# EMG_digital_Part.net
KiCad netlist of a schematic drawn in EAGLE
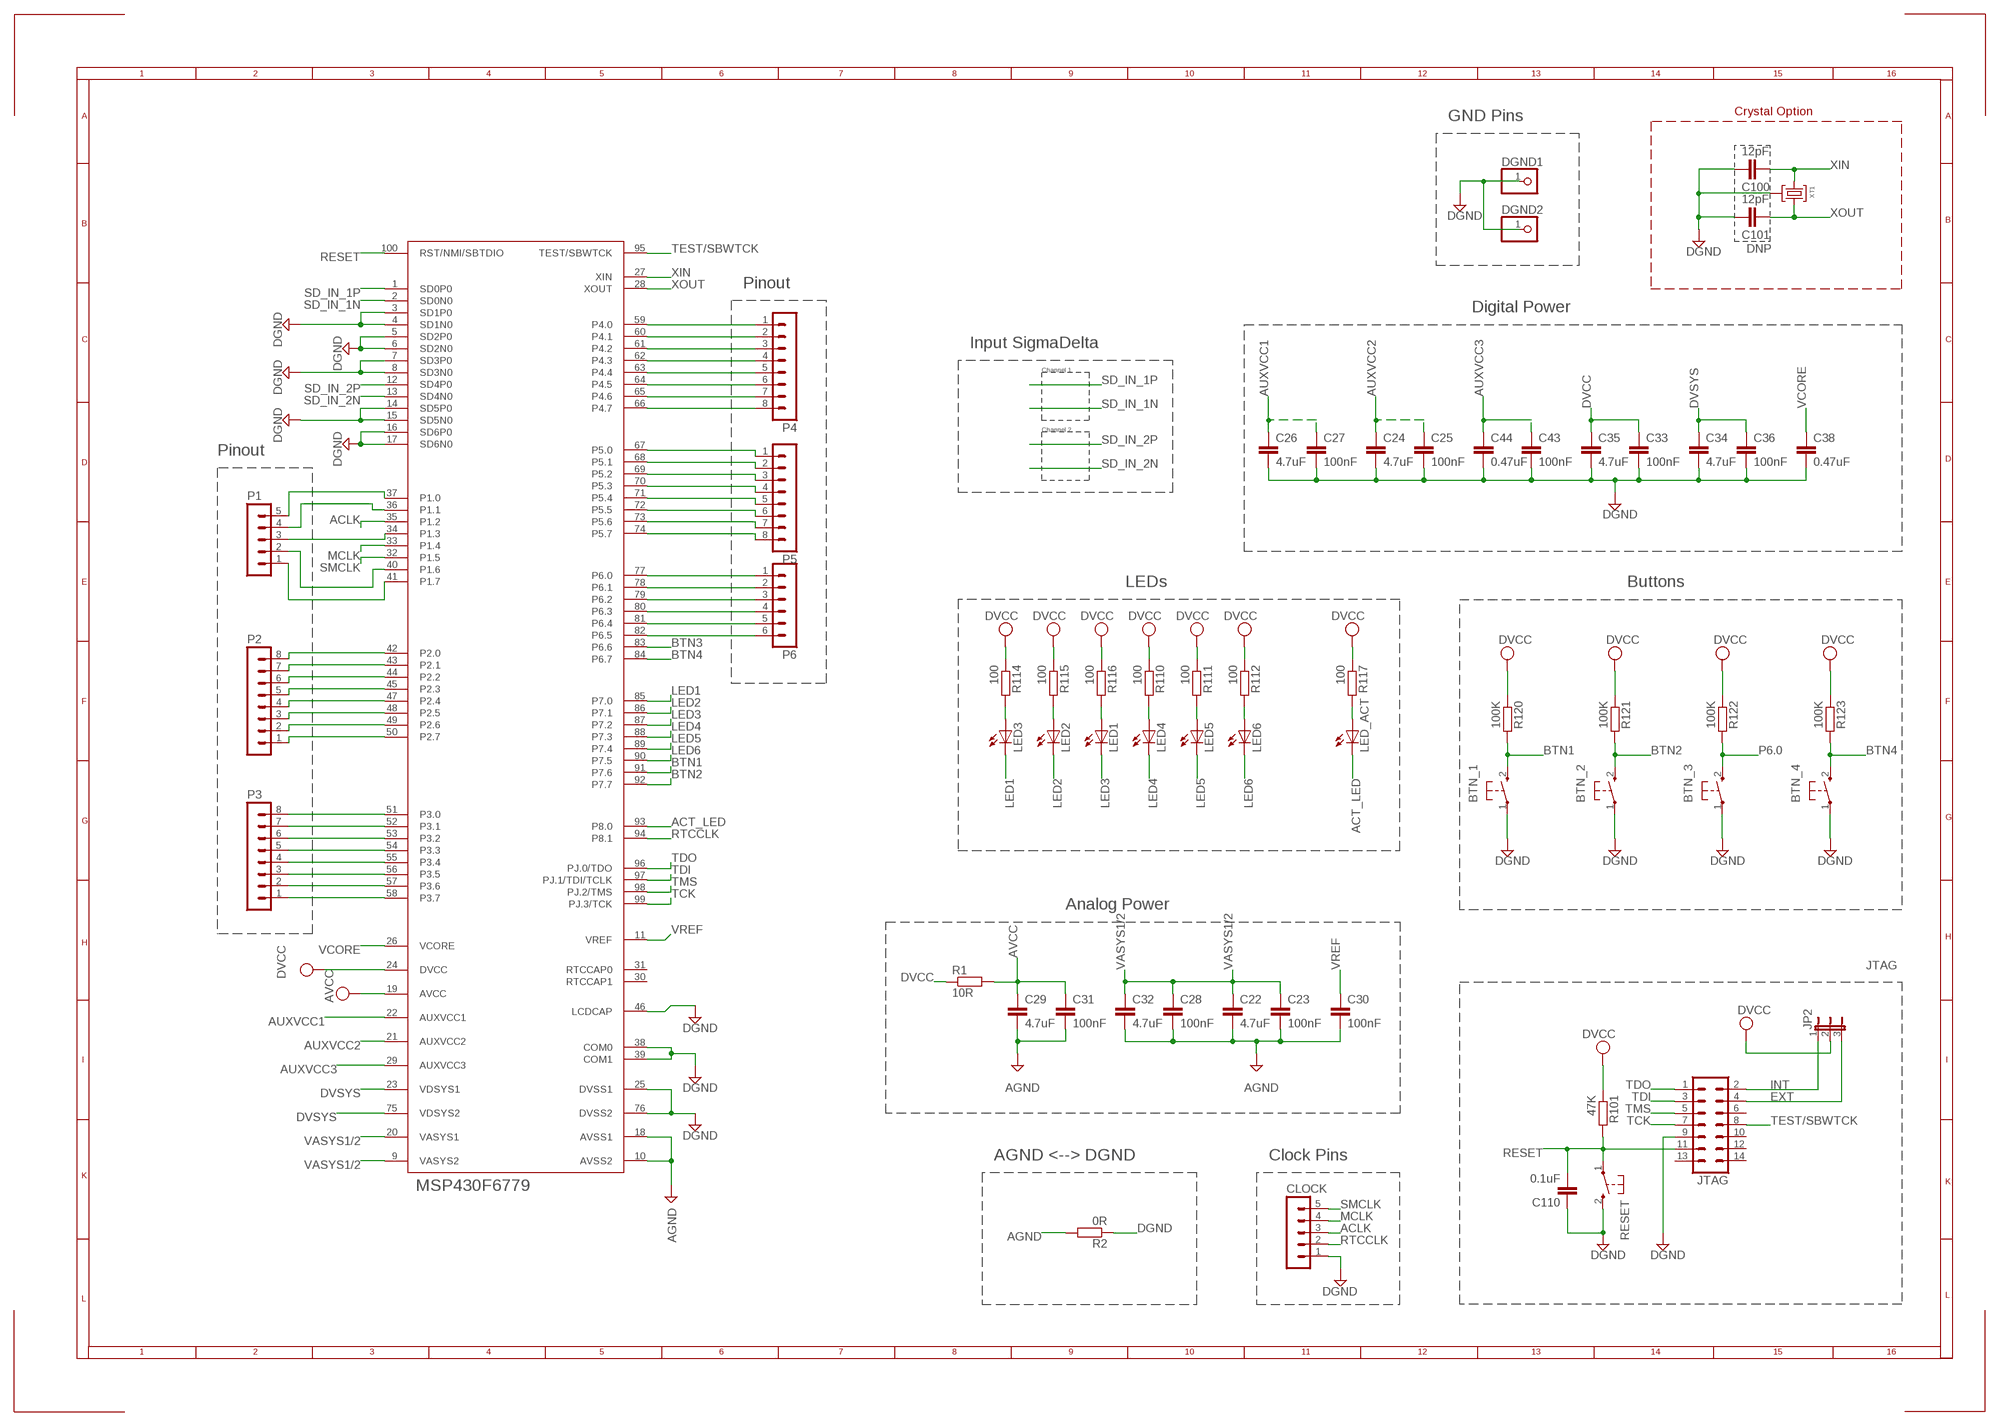
[diagram p0: schematic, sheet 1]

(export (version "E")
  (design (tool "Eeschema 10.0.6"))
  (components
    (comp (ref "BTN_1")
      (value "PB")
      (footprint "eagle-import:PBTH")
      (libsource (lib "eagle-import") (part "PB"))
    )
    (comp (ref "BTN_2")
      (value "PB")
      (footprint "eagle-import:PBTH")
      (libsource (lib "eagle-import") (part "PB"))
    )
    (comp (ref "BTN_3")
      (value "PB")
      (footprint "eagle-import:PBTH")
      (libsource (lib "eagle-import") (part "PB"))
    )
    (comp (ref "BTN_4")
      (value "PB")
      (footprint "eagle-import:PBTH")
      (libsource (lib "eagle-import") (part "PB"))
    )
    (comp (ref "C22")
      (value "4.7uF")
      (footprint "eagle-import:C0805")
      (libsource (lib "eagle-import") (part "C-EUC0805"))
    )
    (comp (ref "C23")
      (value "100nF")
      (footprint "eagle-import:C0805")
      (libsource (lib "eagle-import") (part "C-EUC0805"))
    )
    (comp (ref "C24")
      (value "4.7uF")
      (footprint "eagle-import:C0805")
      (libsource (lib "eagle-import") (part "C-EUC0805"))
    )
    (comp (ref "C25")
      (value "100nF")
      (footprint "eagle-import:C0805")
      (libsource (lib "eagle-import") (part "C-EUC0805"))
    )
    (comp (ref "C26")
      (value "4.7uF")
      (footprint "eagle-import:C0805")
      (libsource (lib "eagle-import") (part "C-EUC0805"))
    )
    (comp (ref "C27")
      (value "100nF")
      (footprint "eagle-import:C0805")
      (libsource (lib "eagle-import") (part "C-EUC0805"))
    )
    (comp (ref "C28")
      (value "100nF")
      (footprint "eagle-import:C0805")
      (libsource (lib "eagle-import") (part "C-EUC0805"))
    )
    (comp (ref "C29")
      (value "4.7uF")
      (footprint "eagle-import:C0805")
      (libsource (lib "eagle-import") (part "C-EUC0805"))
    )
    (comp (ref "C30")
      (value "100nF")
      (footprint "eagle-import:C0805")
      (libsource (lib "eagle-import") (part "C-EUC0805"))
    )
    (comp (ref "C31")
      (value "100nF")
      (footprint "eagle-import:C0805")
      (libsource (lib "eagle-import") (part "C-EUC0805"))
    )
    (comp (ref "C32")
      (value "4.7uF")
      (footprint "eagle-import:C0805")
      (libsource (lib "eagle-import") (part "C-EUC0805"))
    )
    (comp (ref "C33")
      (value "100nF")
      (footprint "eagle-import:C0805")
      (libsource (lib "eagle-import") (part "C-EUC0805"))
    )
    (comp (ref "C34")
      (value "4.7uF")
      (footprint "eagle-import:C0805")
      (libsource (lib "eagle-import") (part "C-EUC0805"))
    )
    (comp (ref "C35")
      (value "4.7uF")
      (footprint "eagle-import:C0805")
      (libsource (lib "eagle-import") (part "C-EUC0805"))
    )
    (comp (ref "C36")
      (value "100nF")
      (footprint "eagle-import:C0805")
      (libsource (lib "eagle-import") (part "C-EUC0805"))
    )
    (comp (ref "C38")
      (value "0.47uF")
      (footprint "eagle-import:C0805")
      (libsource (lib "eagle-import") (part "C-EUC0805"))
    )
    (comp (ref "C43")
      (value "100nF")
      (footprint "eagle-import:C0805")
      (libsource (lib "eagle-import") (part "C-EUC0805"))
    )
    (comp (ref "C44")
      (value "0.47uF")
      (footprint "eagle-import:C0805")
      (libsource (lib "eagle-import") (part "C-EUC0805"))
    )
    (comp (ref "C100")
      (value "12pF")
      (footprint "eagle-import:C0805")
      (libsource (lib "eagle-import") (part "C-EUC0805"))
    )
    (comp (ref "C101")
      (value "12pF")
      (footprint "eagle-import:C0805")
      (libsource (lib "eagle-import") (part "C-EUC0805"))
    )
    (comp (ref "C110")
      (value "0.1uF")
      (footprint "eagle-import:C0805")
      (libsource (lib "eagle-import") (part "C-EUC0805"))
    )
    (comp (ref "CLOCK")
      (value "MA05-1")
      (footprint "eagle-import:MA05-1")
      (libsource (lib "eagle-import") (part "MA05-1"))
    )
    (comp (ref "DGND1")
      (value "PINHD-1X1")
      (footprint "eagle-import:1X01")
      (libsource (lib "eagle-import") (part "PINHD-1X1"))
    )
    (comp (ref "DGND2")
      (value "PINHD-1X1")
      (footprint "eagle-import:1X01")
      (libsource (lib "eagle-import") (part "PINHD-1X1"))
    )
    (comp (ref "JP2")
      (value "JP2E")
      (footprint "eagle-import:JP2")
      (libsource (lib "eagle-import") (part "JP2E"))
    )
    (comp (ref "JTAG")
      (value "ML14")
      (footprint "eagle-import:ML14")
      (libsource (lib "eagle-import") (part "ML14"))
    )
    (comp (ref "LED1")
      (value "LED3MM")
      (footprint "eagle-import:LED3MM")
      (libsource (lib "eagle-import") (part "LED3MM"))
    )
    (comp (ref "LED2")
      (value "LED3MM")
      (footprint "eagle-import:LED3MM")
      (libsource (lib "eagle-import") (part "LED3MM"))
    )
    (comp (ref "LED3")
      (value "LED3MM")
      (footprint "eagle-import:LED3MM")
      (libsource (lib "eagle-import") (part "LED3MM"))
    )
    (comp (ref "LED4")
      (value "LED3MM")
      (footprint "eagle-import:LED3MM")
      (libsource (lib "eagle-import") (part "LED3MM"))
    )
    (comp (ref "LED5")
      (value "LED3MM")
      (footprint "eagle-import:LED3MM")
      (libsource (lib "eagle-import") (part "LED3MM"))
    )
    (comp (ref "LED6")
      (value "LED3MM")
      (footprint "eagle-import:LED3MM")
      (libsource (lib "eagle-import") (part "LED3MM"))
    )
    (comp (ref "LED_ACT")
      (value "LED3MM")
      (footprint "eagle-import:LED3MM")
      (libsource (lib "eagle-import") (part "LED3MM"))
    )
    (comp (ref "P1")
      (value "MA05-1")
      (footprint "eagle-import:MA05-1")
      (libsource (lib "eagle-import") (part "con-lstb_162_MA05-1"))
    )
    (comp (ref "P2")
      (value "MA08-1")
      (footprint "eagle-import:MA08-1")
      (libsource (lib "eagle-import") (part "MA08-1"))
    )
    (comp (ref "P3")
      (value "MA08-1")
      (footprint "eagle-import:MA08-1")
      (libsource (lib "eagle-import") (part "MA08-1"))
    )
    (comp (ref "P4")
      (value "MA08-1")
      (footprint "eagle-import:MA08-1")
      (libsource (lib "eagle-import") (part "MA08-1"))
    )
    (comp (ref "P5")
      (value "MA08-1")
      (footprint "eagle-import:MA08-1")
      (libsource (lib "eagle-import") (part "MA08-1"))
    )
    (comp (ref "P6")
      (value "MA06-1")
      (footprint "eagle-import:MA06-1")
      (libsource (lib "eagle-import") (part "MA06-1"))
    )
    (comp (ref "R1")
      (value "10R")
      (footprint "eagle-import:R0805")
      (libsource (lib "eagle-import") (part "R-EU_R0805"))
    )
    (comp (ref "R2")
      (value "0R")
      (footprint "eagle-import:R0805")
      (libsource (lib "eagle-import") (part "R-EU_R0805"))
    )
    (comp (ref "R101")
      (value "47K")
      (footprint "eagle-import:R0805")
      (libsource (lib "eagle-import") (part "R-EU_R0805"))
    )
    (comp (ref "R110")
      (value "100")
      (footprint "eagle-import:R0805")
      (libsource (lib "eagle-import") (part "R-EU_R0805"))
    )
    (comp (ref "R111")
      (value "100")
      (footprint "eagle-import:R0805")
      (libsource (lib "eagle-import") (part "R-EU_R0805"))
    )
    (comp (ref "R112")
      (value "100")
      (footprint "eagle-import:R0805")
      (libsource (lib "eagle-import") (part "R-EU_R0805"))
    )
    (comp (ref "R114")
      (value "100")
      (footprint "eagle-import:R0805")
      (libsource (lib "eagle-import") (part "R-EU_R0805"))
    )
    (comp (ref "R115")
      (value "100")
      (footprint "eagle-import:R0805")
      (libsource (lib "eagle-import") (part "R-EU_R0805"))
    )
    (comp (ref "R116")
      (value "100")
      (footprint "eagle-import:R0805")
      (libsource (lib "eagle-import") (part "R-EU_R0805"))
    )
    (comp (ref "R117")
      (value "100")
      (footprint "eagle-import:R0805")
      (libsource (lib "eagle-import") (part "R-EU_R0805"))
    )
    (comp (ref "R120")
      (value "100K")
      (footprint "eagle-import:R0805")
      (libsource (lib "eagle-import") (part "R-EU_R0805"))
    )
    (comp (ref "R121")
      (value "100K")
      (footprint "eagle-import:R0805")
      (libsource (lib "eagle-import") (part "R-EU_R0805"))
    )
    (comp (ref "R122")
      (value "100K")
      (footprint "eagle-import:R0805")
      (libsource (lib "eagle-import") (part "R-EU_R0805"))
    )
    (comp (ref "R123")
      (value "100K")
      (footprint "eagle-import:R0805")
      (libsource (lib "eagle-import") (part "R-EU_R0805"))
    )
    (comp (ref "RESET")
      (value "RESET")
      (footprint "eagle-import:PBTH")
      (libsource (lib "eagle-import") (part "PB"))
    )
    (comp (ref "U$1")
      (value "MSP430F6779PZ")
      (footprint "eagle-import:S-PQFP-G100(PZ)")
      (libsource (lib "eagle-import") (part "MSP430F6779PZ"))
    )
    (comp (ref "XT1")
      (value "CM200T")
      (footprint "eagle-import:CM200T")
      (libsource (lib "eagle-import") (part "CM200T"))
    )
  )
  (nets
    (net (code "1") (name "/ACLK") (class "Default")
      (node (ref "CLOCK") (pin "3") (pinfunction "3_3") (pintype "passive"))
      (node (ref "U$1") (pin "35") (pinfunction "P1.2_35") (pintype "bidirectional"))
    )
    (net (code "2") (name "/ACT_LED") (class "Default")
      (node (ref "LED_ACT") (pin "K") (pinfunction "C_K") (pintype "passive"))
      (node (ref "U$1") (pin "93") (pinfunction "P8.0_93") (pintype "bidirectional"))
    )
    (net (code "3") (name "/AUXVCC1") (class "Default")
      (node (ref "C26") (pin "1") (pinfunction "1_1") (pintype "passive"))
      (node (ref "C27") (pin "1") (pinfunction "1_1") (pintype "passive"))
      (node (ref "U$1") (pin "22") (pinfunction "AUXVCC1_22") (pintype "bidirectional"))
    )
    (net (code "4") (name "/AUXVCC2") (class "Default")
      (node (ref "C24") (pin "1") (pinfunction "1_1") (pintype "passive"))
      (node (ref "C25") (pin "1") (pinfunction "1_1") (pintype "passive"))
      (node (ref "U$1") (pin "21") (pinfunction "AUXVCC2_21") (pintype "bidirectional"))
    )
    (net (code "5") (name "/AUXVCC3") (class "Default")
      (node (ref "C43") (pin "1") (pinfunction "1_1") (pintype "passive"))
      (node (ref "C44") (pin "1") (pinfunction "1_1") (pintype "passive"))
      (node (ref "U$1") (pin "29") (pinfunction "AUXVCC3_29") (pintype "bidirectional"))
    )
    (net (code "6") (name "/BTN1") (class "Default")
      (node (ref "BTN_1") (pin "2") (pinfunction "S_2") (pintype "passive"))
      (node (ref "R120") (pin "2") (pinfunction "2_2") (pintype "passive"))
      (node (ref "U$1") (pin "91") (pinfunction "P7.6_91") (pintype "bidirectional"))
    )
    (net (code "7") (name "/BTN2") (class "Default")
      (node (ref "BTN_2") (pin "2") (pinfunction "S_2") (pintype "passive"))
      (node (ref "R121") (pin "2") (pinfunction "2_2") (pintype "passive"))
      (node (ref "U$1") (pin "92") (pinfunction "P7.7_92") (pintype "bidirectional"))
    )
    (net (code "8") (name "/BTN3") (class "Default")
      (node (ref "U$1") (pin "83") (pinfunction "P6.6_83") (pintype "bidirectional"))
    )
    (net (code "9") (name "/BTN4") (class "Default")
      (node (ref "BTN_4") (pin "2") (pinfunction "S_2") (pintype "passive"))
      (node (ref "R123") (pin "2") (pinfunction "2_2") (pintype "passive"))
      (node (ref "U$1") (pin "84") (pinfunction "P6.7_84") (pintype "bidirectional"))
    )
    (net (code "10") (name "/DVSYS") (class "Default")
      (node (ref "C34") (pin "1") (pinfunction "1_1") (pintype "passive"))
      (node (ref "C36") (pin "1") (pinfunction "1_1") (pintype "passive"))
      (node (ref "U$1") (pin "23") (pinfunction "VDSYS1_23") (pintype "bidirectional"))
      (node (ref "U$1") (pin "75") (pinfunction "VDSYS2_75") (pintype "bidirectional"))
    )
    (net (code "11") (name "/EXT") (class "Default")
      (node (ref "JP2") (pin "3") (pinfunction "3_3") (pintype "passive"))
      (node (ref "JTAG") (pin "4") (pinfunction "4_4") (pintype "passive"))
    )
    (net (code "12") (name "/INT") (class "Default")
      (node (ref "JP2") (pin "1") (pinfunction "1_1") (pintype "passive"))
      (node (ref "JTAG") (pin "2") (pinfunction "2_2") (pintype "passive"))
    )
    (net (code "13") (name "/LED1") (class "Default")
      (node (ref "LED3") (pin "K") (pinfunction "C_K") (pintype "passive"))
      (node (ref "U$1") (pin "85") (pinfunction "P7.0_85") (pintype "bidirectional"))
    )
    (net (code "14") (name "/LED2") (class "Default")
      (node (ref "LED2") (pin "K") (pinfunction "C_K") (pintype "passive"))
      (node (ref "U$1") (pin "86") (pinfunction "P7.1_86") (pintype "bidirectional"))
    )
    (net (code "15") (name "/LED3") (class "Default")
      (node (ref "LED1") (pin "K") (pinfunction "C_K") (pintype "passive"))
      (node (ref "U$1") (pin "87") (pinfunction "P7.2_87") (pintype "bidirectional"))
    )
    (net (code "16") (name "/LED4") (class "Default")
      (node (ref "LED4") (pin "K") (pinfunction "C_K") (pintype "passive"))
      (node (ref "U$1") (pin "88") (pinfunction "P7.3_88") (pintype "bidirectional"))
    )
    (net (code "17") (name "/LED5") (class "Default")
      (node (ref "LED5") (pin "K") (pinfunction "C_K") (pintype "passive"))
      (node (ref "U$1") (pin "89") (pinfunction "P7.4_89") (pintype "bidirectional"))
    )
    (net (code "18") (name "/LED6") (class "Default")
      (node (ref "LED6") (pin "K") (pinfunction "C_K") (pintype "passive"))
      (node (ref "U$1") (pin "90") (pinfunction "P7.5_90") (pintype "bidirectional"))
    )
    (net (code "19") (name "/MCLK") (class "Default")
      (node (ref "CLOCK") (pin "4") (pinfunction "4_4") (pintype "passive"))
      (node (ref "U$1") (pin "33") (pinfunction "P1.4_33") (pintype "bidirectional"))
    )
    (net (code "20") (name "/P6.0") (class "Default")
      (node (ref "BTN_3") (pin "2") (pinfunction "S_2") (pintype "passive"))
      (node (ref "P6") (pin "1") (pinfunction "1_1") (pintype "passive"))
      (node (ref "R122") (pin "2") (pinfunction "2_2") (pintype "passive"))
      (node (ref "U$1") (pin "77") (pinfunction "P6.0_77") (pintype "bidirectional"))
    )
    (net (code "21") (name "/RESET") (class "Default")
      (node (ref "C110") (pin "2") (pinfunction "2_2") (pintype "passive"))
      (node (ref "JTAG") (pin "11") (pinfunction "11_11") (pintype "passive"))
      (node (ref "R101") (pin "2") (pinfunction "2_2") (pintype "passive"))
      (node (ref "RESET") (pin "1") (pinfunction "P_1") (pintype "passive"))
      (node (ref "U$1") (pin "100") (pinfunction "RST/NMI/SBTDIO_100") (pintype "bidirectional"))
    )
    (net (code "22") (name "/RTCCLK") (class "Default")
      (node (ref "CLOCK") (pin "2") (pinfunction "2_2") (pintype "passive"))
      (node (ref "U$1") (pin "94") (pinfunction "P8.1_94") (pintype "bidirectional"))
    )
    (net (code "23") (name "/SD_IN_1N") (class "Default")
      (node (ref "U$1") (pin "2") (pinfunction "SD0N0_2") (pintype "bidirectional"))
    )
    (net (code "24") (name "/SD_IN_1P") (class "Default")
      (node (ref "U$1") (pin "1") (pinfunction "SD0P0_1") (pintype "bidirectional"))
    )
    (net (code "25") (name "/SD_IN_2N") (class "Default")
      (node (ref "U$1") (pin "13") (pinfunction "SD4N0_13") (pintype "bidirectional"))
    )
    (net (code "26") (name "/SD_IN_2P") (class "Default")
      (node (ref "U$1") (pin "12") (pinfunction "SD4P0_12") (pintype "bidirectional"))
    )
    (net (code "27") (name "/SMCLK") (class "Default")
      (node (ref "CLOCK") (pin "5") (pinfunction "5_5") (pintype "passive"))
      (node (ref "U$1") (pin "32") (pinfunction "P1.5_32") (pintype "bidirectional"))
    )
    (net (code "28") (name "/TCK") (class "Default")
      (node (ref "JTAG") (pin "7") (pinfunction "7_7") (pintype "passive"))
      (node (ref "U$1") (pin "99") (pinfunction "PJ.3/TCK_99") (pintype "bidirectional"))
    )
    (net (code "29") (name "/TDI") (class "Default")
      (node (ref "JTAG") (pin "3") (pinfunction "3_3") (pintype "passive"))
      (node (ref "U$1") (pin "97") (pinfunction "PJ.1/TDI/TCLK_97") (pintype "bidirectional"))
    )
    (net (code "30") (name "/TDO") (class "Default")
      (node (ref "JTAG") (pin "1") (pinfunction "1_1") (pintype "passive"))
      (node (ref "U$1") (pin "96") (pinfunction "PJ.0/TDO_96") (pintype "bidirectional"))
    )
    (net (code "31") (name "/TEST{slash}SBWTCK") (class "Default")
      (node (ref "JTAG") (pin "8") (pinfunction "8_8") (pintype "passive"))
      (node (ref "U$1") (pin "95") (pinfunction "TEST/SBWTCK_95") (pintype "bidirectional"))
    )
    (net (code "32") (name "/TMS") (class "Default")
      (node (ref "JTAG") (pin "5") (pinfunction "5_5") (pintype "passive"))
      (node (ref "U$1") (pin "98") (pinfunction "PJ.2/TMS_98") (pintype "bidirectional"))
    )
    (net (code "33") (name "/VASYS1{slash}2") (class "Default")
      (node (ref "C22") (pin "1") (pinfunction "1_1") (pintype "passive"))
      (node (ref "C23") (pin "1") (pinfunction "1_1") (pintype "passive"))
      (node (ref "C28") (pin "1") (pinfunction "1_1") (pintype "passive"))
      (node (ref "C32") (pin "1") (pinfunction "1_1") (pintype "passive"))
      (node (ref "U$1") (pin "20") (pinfunction "VASYS1_20") (pintype "bidirectional"))
      (node (ref "U$1") (pin "9") (pinfunction "VASYS2_9") (pintype "bidirectional"))
    )
    (net (code "34") (name "/VCORE") (class "Default")
      (node (ref "C38") (pin "1") (pinfunction "1_1") (pintype "passive"))
      (node (ref "U$1") (pin "26") (pinfunction "VCORE_26") (pintype "bidirectional"))
    )
    (net (code "35") (name "/VREF") (class "Default")
      (node (ref "C30") (pin "1") (pinfunction "1_1") (pintype "passive"))
      (node (ref "U$1") (pin "11") (pinfunction "VREF_11") (pintype "bidirectional"))
    )
    (net (code "36") (name "/XIN") (class "Default")
      (node (ref "C100") (pin "1") (pinfunction "1_1") (pintype "passive"))
      (node (ref "U$1") (pin "27") (pinfunction "XIN_27") (pintype "bidirectional"))
      (node (ref "XT1") (pin "P2") (pinfunction "2_P2") (pintype "bidirectional"))
    )
    (net (code "37") (name "/XOUT") (class "Default")
      (node (ref "C101") (pin "1") (pinfunction "1_1") (pintype "passive"))
      (node (ref "U$1") (pin "28") (pinfunction "XOUT_28") (pintype "bidirectional"))
      (node (ref "XT1") (pin "P1") (pinfunction "1_P1") (pintype "bidirectional"))
    )
    (net (code "38") (name "AGND") (class "Default")
      (node (ref "C22") (pin "2") (pinfunction "2_2") (pintype "passive"))
      (node (ref "C23") (pin "2") (pinfunction "2_2") (pintype "passive"))
      (node (ref "C28") (pin "2") (pinfunction "2_2") (pintype "passive"))
      (node (ref "C29") (pin "2") (pinfunction "2_2") (pintype "passive"))
      (node (ref "C30") (pin "2") (pinfunction "2_2") (pintype "passive"))
      (node (ref "C31") (pin "2") (pinfunction "2_2") (pintype "passive"))
      (node (ref "C32") (pin "2") (pinfunction "2_2") (pintype "passive"))
      (node (ref "R2") (pin "2") (pinfunction "2_2") (pintype "passive"))
      (node (ref "U$1") (pin "10") (pinfunction "AVSS2_10") (pintype "bidirectional"))
      (node (ref "U$1") (pin "18") (pinfunction "AVSS1_18") (pintype "bidirectional"))
    )
    (net (code "39") (name "AVCC") (class "Default")
      (node (ref "C29") (pin "1") (pinfunction "1_1") (pintype "passive"))
      (node (ref "C31") (pin "1") (pinfunction "1_1") (pintype "passive"))
      (node (ref "R1") (pin "2") (pinfunction "2_2") (pintype "passive"))
      (node (ref "U$1") (pin "19") (pinfunction "AVCC_19") (pintype "bidirectional"))
    )
    (net (code "40") (name "DGND") (class "Default")
      (node (ref "BTN_1") (pin "1") (pinfunction "P_1") (pintype "passive"))
      (node (ref "BTN_2") (pin "1") (pinfunction "P_1") (pintype "passive"))
      (node (ref "BTN_3") (pin "1") (pinfunction "P_1") (pintype "passive"))
      (node (ref "BTN_4") (pin "1") (pinfunction "P_1") (pintype "passive"))
      (node (ref "C100") (pin "2") (pinfunction "2_2") (pintype "passive"))
      (node (ref "C101") (pin "2") (pinfunction "2_2") (pintype "passive"))
      (node (ref "C110") (pin "1") (pinfunction "1_1") (pintype "passive"))
      (node (ref "C24") (pin "2") (pinfunction "2_2") (pintype "passive"))
      (node (ref "C25") (pin "2") (pinfunction "2_2") (pintype "passive"))
      (node (ref "C26") (pin "2") (pinfunction "2_2") (pintype "passive"))
      (node (ref "C27") (pin "2") (pinfunction "2_2") (pintype "passive"))
      (node (ref "C33") (pin "2") (pinfunction "2_2") (pintype "passive"))
      (node (ref "C34") (pin "2") (pinfunction "2_2") (pintype "passive"))
      (node (ref "C35") (pin "2") (pinfunction "2_2") (pintype "passive"))
      (node (ref "C36") (pin "2") (pinfunction "2_2") (pintype "passive"))
      (node (ref "C38") (pin "2") (pinfunction "2_2") (pintype "passive"))
      (node (ref "C43") (pin "2") (pinfunction "2_2") (pintype "passive"))
      (node (ref "C44") (pin "2") (pinfunction "2_2") (pintype "passive"))
      (node (ref "CLOCK") (pin "1") (pinfunction "1_1") (pintype "passive"))
      (node (ref "DGND1") (pin "1") (pinfunction "1_1") (pintype "passive"))
      (node (ref "DGND2") (pin "1") (pinfunction "1_1") (pintype "passive"))
      (node (ref "JTAG") (pin "9") (pinfunction "9_9") (pintype "passive"))
      (node (ref "R2") (pin "1") (pinfunction "1_1") (pintype "passive"))
      (node (ref "RESET") (pin "2") (pinfunction "S_2") (pintype "passive"))
      (node (ref "U$1") (pin "14") (pinfunction "SD5P0_14") (pintype "bidirectional"))
      (node (ref "U$1") (pin "15") (pinfunction "SD5N0_15") (pintype "bidirectional"))
      (node (ref "U$1") (pin "16") (pinfunction "SD6P0_16") (pintype "bidirectional"))
      (node (ref "U$1") (pin "17") (pinfunction "SD6N0_17") (pintype "bidirectional"))
      (node (ref "U$1") (pin "25") (pinfunction "DVSS1_25") (pintype "bidirectional"))
      (node (ref "U$1") (pin "3") (pinfunction "SD1P0_3") (pintype "bidirectional"))
      (node (ref "U$1") (pin "38") (pinfunction "COM0_38") (pintype "bidirectional"))
      (node (ref "U$1") (pin "39") (pinfunction "COM1_39") (pintype "bidirectional"))
      (node (ref "U$1") (pin "4") (pinfunction "SD1N0_4") (pintype "bidirectional"))
      (node (ref "U$1") (pin "46") (pinfunction "LCDCAP_46") (pintype "bidirectional"))
      (node (ref "U$1") (pin "5") (pinfunction "SD2P0_5") (pintype "bidirectional"))
      (node (ref "U$1") (pin "6") (pinfunction "SD2N0_6") (pintype "bidirectional"))
      (node (ref "U$1") (pin "7") (pinfunction "SD3P0_7") (pintype "bidirectional"))
      (node (ref "U$1") (pin "76") (pinfunction "DVSS2_76") (pintype "bidirectional"))
      (node (ref "U$1") (pin "8") (pinfunction "SD3N0_8") (pintype "bidirectional"))
      (node (ref "XT1") (pin "P3") (pinfunction "3_P3") (pintype "bidirectional"))
    )
    (net (code "41") (name "DVCC") (class "Default")
      (node (ref "C33") (pin "1") (pinfunction "1_1") (pintype "passive"))
      (node (ref "C35") (pin "1") (pinfunction "1_1") (pintype "passive"))
      (node (ref "JP2") (pin "2") (pinfunction "2_2") (pintype "passive"))
      (node (ref "R1") (pin "1") (pinfunction "1_1") (pintype "passive"))
      (node (ref "R101") (pin "1") (pinfunction "1_1") (pintype "passive"))
      (node (ref "R110") (pin "1") (pinfunction "1_1") (pintype "passive"))
      (node (ref "R111") (pin "1") (pinfunction "1_1") (pintype "passive"))
      (node (ref "R112") (pin "1") (pinfunction "1_1") (pintype "passive"))
      (node (ref "R114") (pin "1") (pinfunction "1_1") (pintype "passive"))
      (node (ref "R115") (pin "1") (pinfunction "1_1") (pintype "passive"))
      (node (ref "R116") (pin "1") (pinfunction "1_1") (pintype "passive"))
      (node (ref "R117") (pin "1") (pinfunction "1_1") (pintype "passive"))
      (node (ref "R120") (pin "1") (pinfunction "1_1") (pintype "passive"))
      (node (ref "R121") (pin "1") (pinfunction "1_1") (pintype "passive"))
      (node (ref "R122") (pin "1") (pinfunction "1_1") (pintype "passive"))
      (node (ref "R123") (pin "1") (pinfunction "1_1") (pintype "passive"))
      (node (ref "U$1") (pin "24") (pinfunction "DVCC_24") (pintype "bidirectional"))
    )
    (net (code "42") (name "Net-(LED1-PadA)") (class "Default")
      (node (ref "LED1") (pin "A") (pinfunction "A_A") (pintype "passive"))
      (node (ref "R116") (pin "2") (pinfunction "2_2") (pintype "passive"))
    )
    (net (code "43") (name "Net-(LED2-PadA)") (class "Default")
      (node (ref "LED2") (pin "A") (pinfunction "A_A") (pintype "passive"))
      (node (ref "R115") (pin "2") (pinfunction "2_2") (pintype "passive"))
    )
    (net (code "44") (name "Net-(LED3-PadA)") (class "Default")
      (node (ref "LED3") (pin "A") (pinfunction "A_A") (pintype "passive"))
      (node (ref "R114") (pin "2") (pinfunction "2_2") (pintype "passive"))
    )
    (net (code "45") (name "Net-(LED4-PadA)") (class "Default")
      (node (ref "LED4") (pin "A") (pinfunction "A_A") (pintype "passive"))
      (node (ref "R110") (pin "2") (pinfunction "2_2") (pintype "passive"))
    )
    (net (code "46") (name "Net-(LED5-PadA)") (class "Default")
      (node (ref "LED5") (pin "A") (pinfunction "A_A") (pintype "passive"))
      (node (ref "R111") (pin "2") (pinfunction "2_2") (pintype "passive"))
    )
    (net (code "47") (name "Net-(LED6-PadA)") (class "Default")
      (node (ref "LED6") (pin "A") (pinfunction "A_A") (pintype "passive"))
      (node (ref "R112") (pin "2") (pinfunction "2_2") (pintype "passive"))
    )
    (net (code "48") (name "Net-(LED_ACT-PadA)") (class "Default")
      (node (ref "LED_ACT") (pin "A") (pinfunction "A_A") (pintype "passive"))
      (node (ref "R117") (pin "2") (pinfunction "2_2") (pintype "passive"))
    )
    (net (code "49") (name "Net-(U$1-P1.0)") (class "Default")
      (node (ref "P1") (pin "5") (pinfunction "5_5") (pintype "passive"))
      (node (ref "U$1") (pin "37") (pinfunction "P1.0_37") (pintype "bidirectional"))
    )
    (net (code "50") (name "Net-(U$1-P1.1)") (class "Default")
      (node (ref "P1") (pin "4") (pinfunction "4_4") (pintype "passive"))
      (node (ref "U$1") (pin "36") (pinfunction "P1.1_36") (pintype "bidirectional"))
    )
    (net (code "51") (name "Net-(U$1-P1.3)") (class "Default")
      (node (ref "P1") (pin "3") (pinfunction "3_3") (pintype "passive"))
      (node (ref "U$1") (pin "34") (pinfunction "P1.3_34") (pintype "bidirectional"))
    )
    (net (code "52") (name "Net-(U$1-P1.6)") (class "Default")
      (node (ref "P1") (pin "2") (pinfunction "2_2") (pintype "passive"))
      (node (ref "U$1") (pin "40") (pinfunction "P1.6_40") (pintype "bidirectional"))
    )
    (net (code "53") (name "Net-(U$1-P1.7)") (class "Default")
      (node (ref "P1") (pin "1") (pinfunction "1_1") (pintype "passive"))
      (node (ref "U$1") (pin "41") (pinfunction "P1.7_41") (pintype "bidirectional"))
    )
    (net (code "54") (name "Net-(U$1-P2.0)") (class "Default")
      (node (ref "P2") (pin "8") (pinfunction "8_8") (pintype "passive"))
      (node (ref "U$1") (pin "42") (pinfunction "P2.0_42") (pintype "bidirectional"))
    )
    (net (code "55") (name "Net-(U$1-P2.1)") (class "Default")
      (node (ref "P2") (pin "7") (pinfunction "7_7") (pintype "passive"))
      (node (ref "U$1") (pin "43") (pinfunction "P2.1_43") (pintype "bidirectional"))
    )
    (net (code "56") (name "Net-(U$1-P2.2)") (class "Default")
      (node (ref "P2") (pin "6") (pinfunction "6_6") (pintype "passive"))
      (node (ref "U$1") (pin "44") (pinfunction "P2.2_44") (pintype "bidirectional"))
    )
    (net (code "57") (name "Net-(U$1-P2.3)") (class "Default")
      (node (ref "P2") (pin "5") (pinfunction "5_5") (pintype "passive"))
      (node (ref "U$1") (pin "45") (pinfunction "P2.3_45") (pintype "bidirectional"))
    )
    (net (code "58") (name "Net-(U$1-P2.4)") (class "Default")
      (node (ref "P2") (pin "4") (pinfunction "4_4") (pintype "passive"))
      (node (ref "U$1") (pin "47") (pinfunction "P2.4_47") (pintype "bidirectional"))
    )
    (net (code "59") (name "Net-(U$1-P2.5)") (class "Default")
      (node (ref "P2") (pin "3") (pinfunction "3_3") (pintype "passive"))
      (node (ref "U$1") (pin "48") (pinfunction "P2.5_48") (pintype "bidirectional"))
    )
    (net (code "60") (name "Net-(U$1-P2.6)") (class "Default")
      (node (ref "P2") (pin "2") (pinfunction "2_2") (pintype "passive"))
      (node (ref "U$1") (pin "49") (pinfunction "P2.6_49") (pintype "bidirectional"))
    )
    (net (code "61") (name "Net-(U$1-P2.7)") (class "Default")
      (node (ref "P2") (pin "1") (pinfunction "1_1") (pintype "passive"))
      (node (ref "U$1") (pin "50") (pinfunction "P2.7_50") (pintype "bidirectional"))
    )
    (net (code "62") (name "Net-(U$1-P3.0)") (class "Default")
      (node (ref "P3") (pin "8") (pinfunction "8_8") (pintype "passive"))
      (node (ref "U$1") (pin "51") (pinfunction "P3.0_51") (pintype "bidirectional"))
    )
    (net (code "63") (name "Net-(U$1-P3.1)") (class "Default")
      (node (ref "P3") (pin "7") (pinfunction "7_7") (pintype "passive"))
      (node (ref "U$1") (pin "52") (pinfunction "P3.1_52") (pintype "bidirectional"))
    )
    (net (code "64") (name "Net-(U$1-P3.2)") (class "Default")
      (node (ref "P3") (pin "6") (pinfunction "6_6") (pintype "passive"))
      (node (ref "U$1") (pin "53") (pinfunction "P3.2_53") (pintype "bidirectional"))
    )
    (net (code "65") (name "Net-(U$1-P3.3)") (class "Default")
      (node (ref "P3") (pin "5") (pinfunction "5_5") (pintype "passive"))
      (node (ref "U$1") (pin "54") (pinfunction "P3.3_54") (pintype "bidirectional"))
    )
    (net (code "66") (name "Net-(U$1-P3.4)") (class "Default")
      (node (ref "P3") (pin "4") (pinfunction "4_4") (pintype "passive"))
      (node (ref "U$1") (pin "55") (pinfunction "P3.4_55") (pintype "bidirectional"))
    )
    (net (code "67") (name "Net-(U$1-P3.5)") (class "Default")
      (node (ref "P3") (pin "3") (pinfunction "3_3") (pintype "passive"))
      (node (ref "U$1") (pin "56") (pinfunction "P3.5_56") (pintype "bidirectional"))
    )
    (net (code "68") (name "Net-(U$1-P3.6)") (class "Default")
      (node (ref "P3") (pin "2") (pinfunction "2_2") (pintype "passive"))
      (node (ref "U$1") (pin "57") (pinfunction "P3.6_57") (pintype "bidirectional"))
    )
    (net (code "69") (name "Net-(U$1-P3.7)") (class "Default")
      (node (ref "P3") (pin "1") (pinfunction "1_1") (pintype "passive"))
      (node (ref "U$1") (pin "58") (pinfunction "P3.7_58") (pintype "bidirectional"))
    )
    (net (code "70") (name "Net-(U$1-P4.0)") (class "Default")
      (node (ref "P4") (pin "1") (pinfunction "1_1") (pintype "passive"))
      (node (ref "U$1") (pin "59") (pinfunction "P4.0_59") (pintype "bidirectional"))
    )
    (net (code "71") (name "Net-(U$1-P4.1)") (class "Default")
      (node (ref "P4") (pin "2") (pinfunction "2_2") (pintype "passive"))
      (node (ref "U$1") (pin "60") (pinfunction "P4.1_60") (pintype "bidirectional"))
    )
    (net (code "72") (name "Net-(U$1-P4.2)") (class "Default")
      (node (ref "P4") (pin "3") (pinfunction "3_3") (pintype "passive"))
      (node (ref "U$1") (pin "61") (pinfunction "P4.2_61") (pintype "bidirectional"))
    )
    (net (code "73") (name "Net-(U$1-P4.3)") (class "Default")
      (node (ref "P4") (pin "4") (pinfunction "4_4") (pintype "passive"))
      (node (ref "U$1") (pin "62") (pinfunction "P4.3_62") (pintype "bidirectional"))
    )
    (net (code "74") (name "Net-(U$1-P4.4)") (class "Default")
      (node (ref "P4") (pin "5") (pinfunction "5_5") (pintype "passive"))
      (node (ref "U$1") (pin "63") (pinfunction "P4.4_63") (pintype "bidirectional"))
    )
    (net (code "75") (name "Net-(U$1-P4.5)") (class "Default")
      (node (ref "P4") (pin "6") (pinfunction "6_6") (pintype "passive"))
      (node (ref "U$1") (pin "64") (pinfunction "P4.5_64") (pintype "bidirectional"))
    )
    (net (code "76") (name "Net-(U$1-P4.6)") (class "Default")
      (node (ref "P4") (pin "7") (pinfunction "7_7") (pintype "passive"))
      (node (ref "U$1") (pin "65") (pinfunction "P4.6_65") (pintype "bidirectional"))
    )
    (net (code "77") (name "Net-(U$1-P4.7)") (class "Default")
      (node (ref "P4") (pin "8") (pinfunction "8_8") (pintype "passive"))
      (node (ref "U$1") (pin "66") (pinfunction "P4.7_66") (pintype "bidirectional"))
    )
    (net (code "78") (name "Net-(U$1-P5.0)") (class "Default")
      (node (ref "P5") (pin "1") (pinfunction "1_1") (pintype "passive"))
      (node (ref "U$1") (pin "67") (pinfunction "P5.0_67") (pintype "bidirectional"))
    )
    (net (code "79") (name "Net-(U$1-P5.1)") (class "Default")
      (node (ref "P5") (pin "2") (pinfunction "2_2") (pintype "passive"))
      (node (ref "U$1") (pin "68") (pinfunction "P5.1_68") (pintype "bidirectional"))
    )
    (net (code "80") (name "Net-(U$1-P5.2)") (class "Default")
      (node (ref "P5") (pin "3") (pinfunction "3_3") (pintype "passive"))
      (node (ref "U$1") (pin "69") (pinfunction "P5.2_69") (pintype "bidirectional"))
    )
    (net (code "81") (name "Net-(U$1-P5.3)") (class "Default")
      (node (ref "P5") (pin "4") (pinfunction "4_4") (pintype "passive"))
      (node (ref "U$1") (pin "70") (pinfunction "P5.3_70") (pintype "bidirectional"))
    )
    (net (code "82") (name "Net-(U$1-P5.4)") (class "Default")
      (node (ref "P5") (pin "5") (pinfunction "5_5") (pintype "passive"))
      (node (ref "U$1") (pin "71") (pinfunction "P5.4_71") (pintype "bidirectional"))
    )
    (net (code "83") (name "Net-(U$1-P5.5)") (class "Default")
      (node (ref "P5") (pin "6") (pinfunction "6_6") (pintype "passive"))
      (node (ref "U$1") (pin "72") (pinfunction "P5.5_72") (pintype "bidirectional"))
    )
    (net (code "84") (name "Net-(U$1-P5.6)") (class "Default")
      (node (ref "P5") (pin "7") (pinfunction "7_7") (pintype "passive"))
      (node (ref "U$1") (pin "73") (pinfunction "P5.6_73") (pintype "bidirectional"))
    )
    (net (code "85") (name "Net-(U$1-P5.7)") (class "Default")
      (node (ref "P5") (pin "8") (pinfunction "8_8") (pintype "passive"))
      (node (ref "U$1") (pin "74") (pinfunction "P5.7_74") (pintype "bidirectional"))
    )
    (net (code "86") (name "Net-(U$1-P6.1)") (class "Default")
      (node (ref "P6") (pin "2") (pinfunction "2_2") (pintype "passive"))
      (node (ref "U$1") (pin "78") (pinfunction "P6.1_78") (pintype "bidirectional"))
    )
    (net (code "87") (name "Net-(U$1-P6.2)") (class "Default")
      (node (ref "P6") (pin "3") (pinfunction "3_3") (pintype "passive"))
      (node (ref "U$1") (pin "79") (pinfunction "P6.2_79") (pintype "bidirectional"))
    )
    (net (code "88") (name "Net-(U$1-P6.3)") (class "Default")
      (node (ref "P6") (pin "4") (pinfunction "4_4") (pintype "passive"))
      (node (ref "U$1") (pin "80") (pinfunction "P6.3_80") (pintype "bidirectional"))
    )
    (net (code "89") (name "Net-(U$1-P6.4)") (class "Default")
      (node (ref "P6") (pin "5") (pinfunction "5_5") (pintype "passive"))
      (node (ref "U$1") (pin "81") (pinfunction "P6.4_81") (pintype "bidirectional"))
    )
    (net (code "90") (name "Net-(U$1-P6.5)") (class "Default")
      (node (ref "P6") (pin "6") (pinfunction "6_6") (pintype "passive"))
      (node (ref "U$1") (pin "82") (pinfunction "P6.5_82") (pintype "bidirectional"))
    )
    (net (code "91") (name "unconnected-(JTAG-Pad6)") (class "Default")
      (node (ref "JTAG") (pin "6") (pinfunction "6_6") (pintype "passive"))
    )
    (net (code "92") (name "unconnected-(JTAG-Pad10)") (class "Default")
      (node (ref "JTAG") (pin "10") (pinfunction "10_10") (pintype "passive"))
    )
    (net (code "93") (name "unconnected-(JTAG-Pad12)") (class "Default")
      (node (ref "JTAG") (pin "12") (pinfunction "12_12") (pintype "passive"))
    )
    (net (code "94") (name "unconnected-(JTAG-Pad13)") (class "Default")
      (node (ref "JTAG") (pin "13") (pinfunction "13_13") (pintype "passive"))
    )
    (net (code "95") (name "unconnected-(JTAG-Pad14)") (class "Default")
      (node (ref "JTAG") (pin "14") (pinfunction "14_14") (pintype "passive"))
    )
    (net (code "96") (name "unconnected-(U$1-RTCCAP0-Pad31)") (class "Default")
      (node (ref "U$1") (pin "31") (pinfunction "RTCCAP0_31") (pintype "bidirectional"))
    )
    (net (code "97") (name "unconnected-(U$1-RTCCAP1-Pad30)") (class "Default")
      (node (ref "U$1") (pin "30") (pinfunction "RTCCAP1_30") (pintype "bidirectional"))
    )
  )
)
